# year-shift-r1.net
KiCad netlist of a schematic drawn in EAGLE
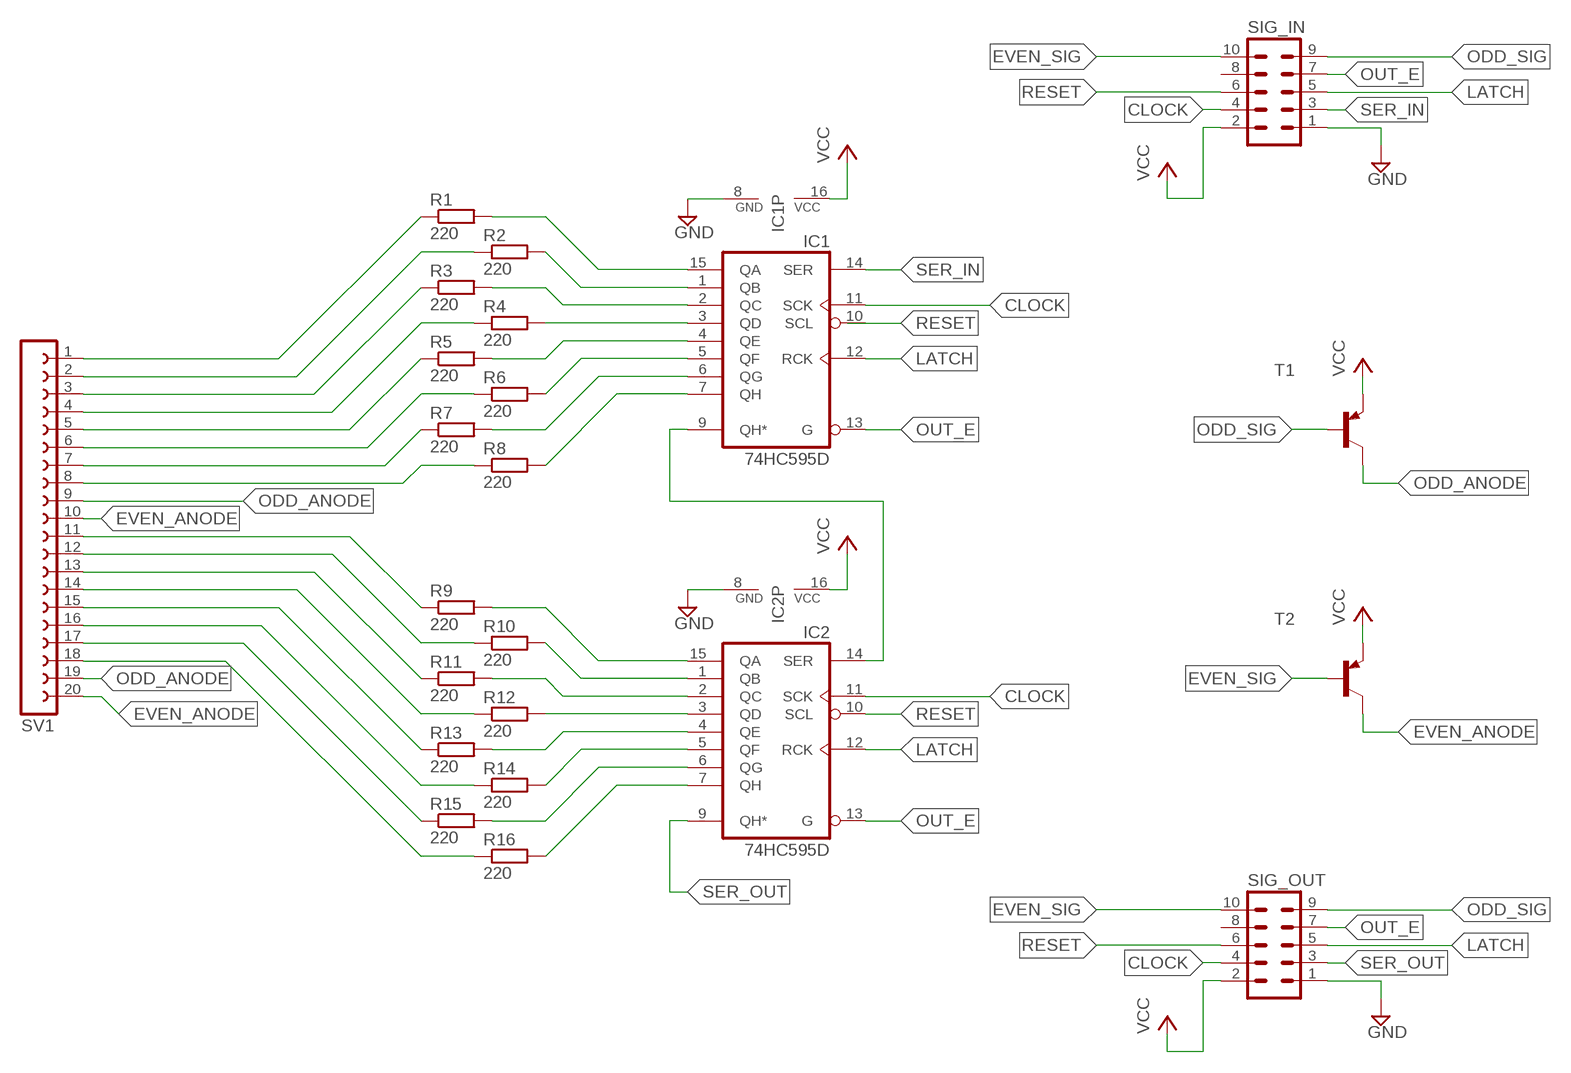
[diagram p0: schematic, sheet 1]

(export (version "E")
  (design (tool "Eeschema 10.0.6"))
  (components
    (comp (ref "IC1")
      (value "74HC595D")
      (footprint "eagle-import:SO16")
      (libsource (lib "eagle-import") (part "74595DHC"))
    )
    (comp (ref "IC2")
      (value "74HC595D")
      (footprint "eagle-import:SO16")
      (libsource (lib "eagle-import") (part "74595DHC"))
    )
    (comp (ref "R1")
      (value "220")
      (footprint "eagle-import:R0805")
      (libsource (lib "eagle-import") (part "R-EU_R0805"))
    )
    (comp (ref "R2")
      (value "220")
      (footprint "eagle-import:R0805")
      (libsource (lib "eagle-import") (part "R-EU_R0805"))
    )
    (comp (ref "R3")
      (value "220")
      (footprint "eagle-import:R0805")
      (libsource (lib "eagle-import") (part "R-EU_R0805"))
    )
    (comp (ref "R4")
      (value "220")
      (footprint "eagle-import:R0805")
      (libsource (lib "eagle-import") (part "R-EU_R0805"))
    )
    (comp (ref "R5")
      (value "220")
      (footprint "eagle-import:R0805")
      (libsource (lib "eagle-import") (part "R-EU_R0805"))
    )
    (comp (ref "R6")
      (value "220")
      (footprint "eagle-import:R0805")
      (libsource (lib "eagle-import") (part "R-EU_R0805"))
    )
    (comp (ref "R7")
      (value "220")
      (footprint "eagle-import:R0805")
      (libsource (lib "eagle-import") (part "R-EU_R0805"))
    )
    (comp (ref "R8")
      (value "220")
      (footprint "eagle-import:R0805")
      (libsource (lib "eagle-import") (part "R-EU_R0805"))
    )
    (comp (ref "R9")
      (value "220")
      (footprint "eagle-import:R0805")
      (libsource (lib "eagle-import") (part "R-EU_R0805"))
    )
    (comp (ref "R10")
      (value "220")
      (footprint "eagle-import:R0805")
      (libsource (lib "eagle-import") (part "R-EU_R0805"))
    )
    (comp (ref "R11")
      (value "220")
      (footprint "eagle-import:R0805")
      (libsource (lib "eagle-import") (part "R-EU_R0805"))
    )
    (comp (ref "R12")
      (value "220")
      (footprint "eagle-import:R0805")
      (libsource (lib "eagle-import") (part "R-EU_R0805"))
    )
    (comp (ref "R13")
      (value "220")
      (footprint "eagle-import:R0805")
      (libsource (lib "eagle-import") (part "R-EU_R0805"))
    )
    (comp (ref "R14")
      (value "220")
      (footprint "eagle-import:R0805")
      (libsource (lib "eagle-import") (part "R-EU_R0805"))
    )
    (comp (ref "R15")
      (value "220")
      (footprint "eagle-import:R0805")
      (libsource (lib "eagle-import") (part "R-EU_R0805"))
    )
    (comp (ref "R16")
      (value "220")
      (footprint "eagle-import:R0805")
      (libsource (lib "eagle-import") (part "R-EU_R0805"))
    )
    (comp (ref "SIG_IN")
      (value "MA05-2")
      (footprint "eagle-import:MA05-2")
      (libsource (lib "eagle-import") (part "MA05-2"))
    )
    (comp (ref "SIG_OUT")
      (value "MA05-2")
      (footprint "eagle-import:MA05-2")
      (libsource (lib "eagle-import") (part "MA05-2"))
    )
    (comp (ref "SV1")
      (value "FE20-1")
      (footprint "eagle-import:FE20")
      (libsource (lib "eagle-import") (part "FE20-1"))
    )
    (comp (ref "T1")
      (value "BC557B-PNP-TO92-EBC")
      (footprint "eagle-import:TO92-EBC")
      (libsource (lib "eagle-import") (part "-PNP-TO92-EBCBC557B"))
    )
    (comp (ref "T2")
      (value "BC557B-PNP-TO92-EBC")
      (footprint "eagle-import:TO92-EBC")
      (libsource (lib "eagle-import") (part "-PNP-TO92-EBCBC557B"))
    )
  )
  (nets
    (net (code "1") (name "CLOCK") (class "Default")
      (node (ref "IC1") (pin "11") (pinfunction "SCK_11") (pintype "input"))
      (node (ref "IC2") (pin "11") (pinfunction "SCK_11") (pintype "input"))
      (node (ref "SIG_IN") (pin "4") (pinfunction "4_4") (pintype "passive"))
      (node (ref "SIG_OUT") (pin "4") (pinfunction "4_4") (pintype "passive"))
    )
    (net (code "2") (name "EVEN_ANODE") (class "Default")
      (node (ref "SV1") (pin "10") (pinfunction "10_10") (pintype "passive"))
      (node (ref "SV1") (pin "20") (pinfunction "20_20") (pintype "passive"))
      (node (ref "T2") (pin "C") (pinfunction "C_C") (pintype "passive"))
    )
    (net (code "3") (name "EVEN_SIG") (class "Default")
      (node (ref "SIG_IN") (pin "10") (pinfunction "10_10") (pintype "passive"))
      (node (ref "SIG_OUT") (pin "10") (pinfunction "10_10") (pintype "passive"))
      (node (ref "T2") (pin "B") (pinfunction "B_B") (pintype "passive"))
    )
    (net (code "4") (name "GND") (class "Default")
      (node (ref "IC1") (pin "8") (pinfunction "GND_8") (pintype "power_in"))
      (node (ref "IC2") (pin "8") (pinfunction "GND_8") (pintype "power_in"))
      (node (ref "SIG_IN") (pin "1") (pinfunction "1_1") (pintype "passive"))
      (node (ref "SIG_OUT") (pin "1") (pinfunction "1_1") (pintype "passive"))
    )
    (net (code "5") (name "LATCH") (class "Default")
      (node (ref "IC1") (pin "12") (pinfunction "RCK_12") (pintype "input"))
      (node (ref "IC2") (pin "12") (pinfunction "RCK_12") (pintype "input"))
      (node (ref "SIG_IN") (pin "5") (pinfunction "5_5") (pintype "passive"))
      (node (ref "SIG_OUT") (pin "5") (pinfunction "5_5") (pintype "passive"))
    )
    (net (code "6") (name "Net-(IC1A-QA)") (class "Default")
      (node (ref "IC1") (pin "15") (pinfunction "QA_15") (pintype "tri_state"))
      (node (ref "R1") (pin "2") (pinfunction "2_2") (pintype "passive"))
    )
    (net (code "7") (name "Net-(IC1A-QB)") (class "Default")
      (node (ref "IC1") (pin "1") (pinfunction "QB_1") (pintype "tri_state"))
      (node (ref "R2") (pin "2") (pinfunction "2_2") (pintype "passive"))
    )
    (net (code "8") (name "Net-(IC1A-QC)") (class "Default")
      (node (ref "IC1") (pin "2") (pinfunction "QC_2") (pintype "tri_state"))
      (node (ref "R3") (pin "2") (pinfunction "2_2") (pintype "passive"))
    )
    (net (code "9") (name "Net-(IC1A-QD)") (class "Default")
      (node (ref "IC1") (pin "3") (pinfunction "QD_3") (pintype "tri_state"))
      (node (ref "R4") (pin "2") (pinfunction "2_2") (pintype "passive"))
    )
    (net (code "10") (name "Net-(IC1A-QE)") (class "Default")
      (node (ref "IC1") (pin "4") (pinfunction "QE_4") (pintype "tri_state"))
      (node (ref "R5") (pin "2") (pinfunction "2_2") (pintype "passive"))
    )
    (net (code "11") (name "Net-(IC1A-QF)") (class "Default")
      (node (ref "IC1") (pin "5") (pinfunction "QF_5") (pintype "tri_state"))
      (node (ref "R6") (pin "2") (pinfunction "2_2") (pintype "passive"))
    )
    (net (code "12") (name "Net-(IC1A-QG)") (class "Default")
      (node (ref "IC1") (pin "6") (pinfunction "QG_6") (pintype "tri_state"))
      (node (ref "R7") (pin "2") (pinfunction "2_2") (pintype "passive"))
    )
    (net (code "13") (name "Net-(IC1A-QH)") (class "Default")
      (node (ref "IC1") (pin "7") (pinfunction "QH_7") (pintype "tri_state"))
      (node (ref "R8") (pin "2") (pinfunction "2_2") (pintype "passive"))
    )
    (net (code "14") (name "Net-(IC1A-QH*)") (class "Default")
      (node (ref "IC1") (pin "9") (pinfunction "QH*_9") (pintype "tri_state"))
      (node (ref "IC2") (pin "14") (pinfunction "SER_14") (pintype "input"))
    )
    (net (code "15") (name "Net-(IC2A-QA)") (class "Default")
      (node (ref "IC2") (pin "15") (pinfunction "QA_15") (pintype "tri_state"))
      (node (ref "R9") (pin "2") (pinfunction "2_2") (pintype "passive"))
    )
    (net (code "16") (name "Net-(IC2A-QB)") (class "Default")
      (node (ref "IC2") (pin "1") (pinfunction "QB_1") (pintype "tri_state"))
      (node (ref "R10") (pin "2") (pinfunction "2_2") (pintype "passive"))
    )
    (net (code "17") (name "Net-(IC2A-QC)") (class "Default")
      (node (ref "IC2") (pin "2") (pinfunction "QC_2") (pintype "tri_state"))
      (node (ref "R11") (pin "2") (pinfunction "2_2") (pintype "passive"))
    )
    (net (code "18") (name "Net-(IC2A-QD)") (class "Default")
      (node (ref "IC2") (pin "3") (pinfunction "QD_3") (pintype "tri_state"))
      (node (ref "R12") (pin "2") (pinfunction "2_2") (pintype "passive"))
    )
    (net (code "19") (name "Net-(IC2A-QE)") (class "Default")
      (node (ref "IC2") (pin "4") (pinfunction "QE_4") (pintype "tri_state"))
      (node (ref "R13") (pin "2") (pinfunction "2_2") (pintype "passive"))
    )
    (net (code "20") (name "Net-(IC2A-QF)") (class "Default")
      (node (ref "IC2") (pin "5") (pinfunction "QF_5") (pintype "tri_state"))
      (node (ref "R14") (pin "2") (pinfunction "2_2") (pintype "passive"))
    )
    (net (code "21") (name "Net-(IC2A-QG)") (class "Default")
      (node (ref "IC2") (pin "6") (pinfunction "QG_6") (pintype "tri_state"))
      (node (ref "R15") (pin "2") (pinfunction "2_2") (pintype "passive"))
    )
    (net (code "22") (name "Net-(IC2A-QH)") (class "Default")
      (node (ref "IC2") (pin "7") (pinfunction "QH_7") (pintype "tri_state"))
      (node (ref "R16") (pin "2") (pinfunction "2_2") (pintype "passive"))
    )
    (net (code "23") (name "Net-(R1-Pad1)") (class "Default")
      (node (ref "R1") (pin "1") (pinfunction "1_1") (pintype "passive"))
      (node (ref "SV1") (pin "1") (pinfunction "1_1") (pintype "passive"))
    )
    (net (code "24") (name "Net-(R2-Pad1)") (class "Default")
      (node (ref "R2") (pin "1") (pinfunction "1_1") (pintype "passive"))
      (node (ref "SV1") (pin "2") (pinfunction "2_2") (pintype "passive"))
    )
    (net (code "25") (name "Net-(R3-Pad1)") (class "Default")
      (node (ref "R3") (pin "1") (pinfunction "1_1") (pintype "passive"))
      (node (ref "SV1") (pin "3") (pinfunction "3_3") (pintype "passive"))
    )
    (net (code "26") (name "Net-(R4-Pad1)") (class "Default")
      (node (ref "R4") (pin "1") (pinfunction "1_1") (pintype "passive"))
      (node (ref "SV1") (pin "4") (pinfunction "4_4") (pintype "passive"))
    )
    (net (code "27") (name "Net-(R5-Pad1)") (class "Default")
      (node (ref "R5") (pin "1") (pinfunction "1_1") (pintype "passive"))
      (node (ref "SV1") (pin "5") (pinfunction "5_5") (pintype "passive"))
    )
    (net (code "28") (name "Net-(R6-Pad1)") (class "Default")
      (node (ref "R6") (pin "1") (pinfunction "1_1") (pintype "passive"))
      (node (ref "SV1") (pin "6") (pinfunction "6_6") (pintype "passive"))
    )
    (net (code "29") (name "Net-(R7-Pad1)") (class "Default")
      (node (ref "R7") (pin "1") (pinfunction "1_1") (pintype "passive"))
      (node (ref "SV1") (pin "7") (pinfunction "7_7") (pintype "passive"))
    )
    (net (code "30") (name "Net-(R8-Pad1)") (class "Default")
      (node (ref "R8") (pin "1") (pinfunction "1_1") (pintype "passive"))
      (node (ref "SV1") (pin "8") (pinfunction "8_8") (pintype "passive"))
    )
    (net (code "31") (name "Net-(R9-Pad1)") (class "Default")
      (node (ref "R9") (pin "1") (pinfunction "1_1") (pintype "passive"))
      (node (ref "SV1") (pin "11") (pinfunction "11_11") (pintype "passive"))
    )
    (net (code "32") (name "Net-(R10-Pad1)") (class "Default")
      (node (ref "R10") (pin "1") (pinfunction "1_1") (pintype "passive"))
      (node (ref "SV1") (pin "12") (pinfunction "12_12") (pintype "passive"))
    )
    (net (code "33") (name "Net-(R11-Pad1)") (class "Default")
      (node (ref "R11") (pin "1") (pinfunction "1_1") (pintype "passive"))
      (node (ref "SV1") (pin "13") (pinfunction "13_13") (pintype "passive"))
    )
    (net (code "34") (name "Net-(R12-Pad1)") (class "Default")
      (node (ref "R12") (pin "1") (pinfunction "1_1") (pintype "passive"))
      (node (ref "SV1") (pin "14") (pinfunction "14_14") (pintype "passive"))
    )
    (net (code "35") (name "Net-(R13-Pad1)") (class "Default")
      (node (ref "R13") (pin "1") (pinfunction "1_1") (pintype "passive"))
      (node (ref "SV1") (pin "15") (pinfunction "15_15") (pintype "passive"))
    )
    (net (code "36") (name "Net-(R14-Pad1)") (class "Default")
      (node (ref "R14") (pin "1") (pinfunction "1_1") (pintype "passive"))
      (node (ref "SV1") (pin "16") (pinfunction "16_16") (pintype "passive"))
    )
    (net (code "37") (name "Net-(R15-Pad1)") (class "Default")
      (node (ref "R15") (pin "1") (pinfunction "1_1") (pintype "passive"))
      (node (ref "SV1") (pin "17") (pinfunction "17_17") (pintype "passive"))
    )
    (net (code "38") (name "Net-(R16-Pad1)") (class "Default")
      (node (ref "R16") (pin "1") (pinfunction "1_1") (pintype "passive"))
      (node (ref "SV1") (pin "18") (pinfunction "18_18") (pintype "passive"))
    )
    (net (code "39") (name "ODD_ANODE") (class "Default")
      (node (ref "SV1") (pin "19") (pinfunction "19_19") (pintype "passive"))
      (node (ref "SV1") (pin "9") (pinfunction "9_9") (pintype "passive"))
      (node (ref "T1") (pin "C") (pinfunction "C_C") (pintype "passive"))
    )
    (net (code "40") (name "ODD_SIG") (class "Default")
      (node (ref "SIG_IN") (pin "9") (pinfunction "9_9") (pintype "passive"))
      (node (ref "SIG_OUT") (pin "9") (pinfunction "9_9") (pintype "passive"))
      (node (ref "T1") (pin "B") (pinfunction "B_B") (pintype "passive"))
    )
    (net (code "41") (name "OUT_E") (class "Default")
      (node (ref "IC1") (pin "13") (pinfunction "G_13") (pintype "input"))
      (node (ref "IC2") (pin "13") (pinfunction "G_13") (pintype "input"))
      (node (ref "SIG_IN") (pin "7") (pinfunction "7_7") (pintype "passive"))
      (node (ref "SIG_OUT") (pin "7") (pinfunction "7_7") (pintype "passive"))
    )
    (net (code "42") (name "RESET") (class "Default")
      (node (ref "IC2") (pin "10") (pinfunction "SCL_10") (pintype "input"))
      (node (ref "SIG_IN") (pin "6") (pinfunction "6_6") (pintype "passive"))
      (node (ref "SIG_OUT") (pin "6") (pinfunction "6_6") (pintype "passive"))
    )
    (net (code "43") (name "SER_IN") (class "Default")
      (node (ref "IC1") (pin "14") (pinfunction "SER_14") (pintype "input"))
      (node (ref "SIG_IN") (pin "3") (pinfunction "3_3") (pintype "passive"))
    )
    (net (code "44") (name "SER_OUT") (class "Default")
      (node (ref "IC2") (pin "9") (pinfunction "QH*_9") (pintype "tri_state"))
      (node (ref "SIG_OUT") (pin "3") (pinfunction "3_3") (pintype "passive"))
    )
    (net (code "45") (name "VCC") (class "Default")
      (node (ref "IC1") (pin "16") (pinfunction "VCC_16") (pintype "power_in"))
      (node (ref "IC2") (pin "16") (pinfunction "VCC_16") (pintype "power_in"))
      (node (ref "SIG_IN") (pin "2") (pinfunction "2_2") (pintype "passive"))
      (node (ref "SIG_OUT") (pin "2") (pinfunction "2_2") (pintype "passive"))
      (node (ref "T1") (pin "E") (pinfunction "E_E") (pintype "passive"))
      (node (ref "T2") (pin "E") (pinfunction "E_E") (pintype "passive"))
    )
    (net (code "46") (name "unconnected-(IC1A-SCL-Pad10)") (class "Default")
      (node (ref "IC1") (pin "10") (pinfunction "SCL_10") (pintype "input"))
    )
    (net (code "47") (name "unconnected-(SIG_IN-Pad8)") (class "Default")
      (node (ref "SIG_IN") (pin "8") (pinfunction "8_8") (pintype "passive"))
    )
    (net (code "48") (name "unconnected-(SIG_OUT-Pad8)") (class "Default")
      (node (ref "SIG_OUT") (pin "8") (pinfunction "8_8") (pintype "passive"))
    )
  )
)
